# simulador.net
KiCad netlist of a schematic drawn in EAGLE
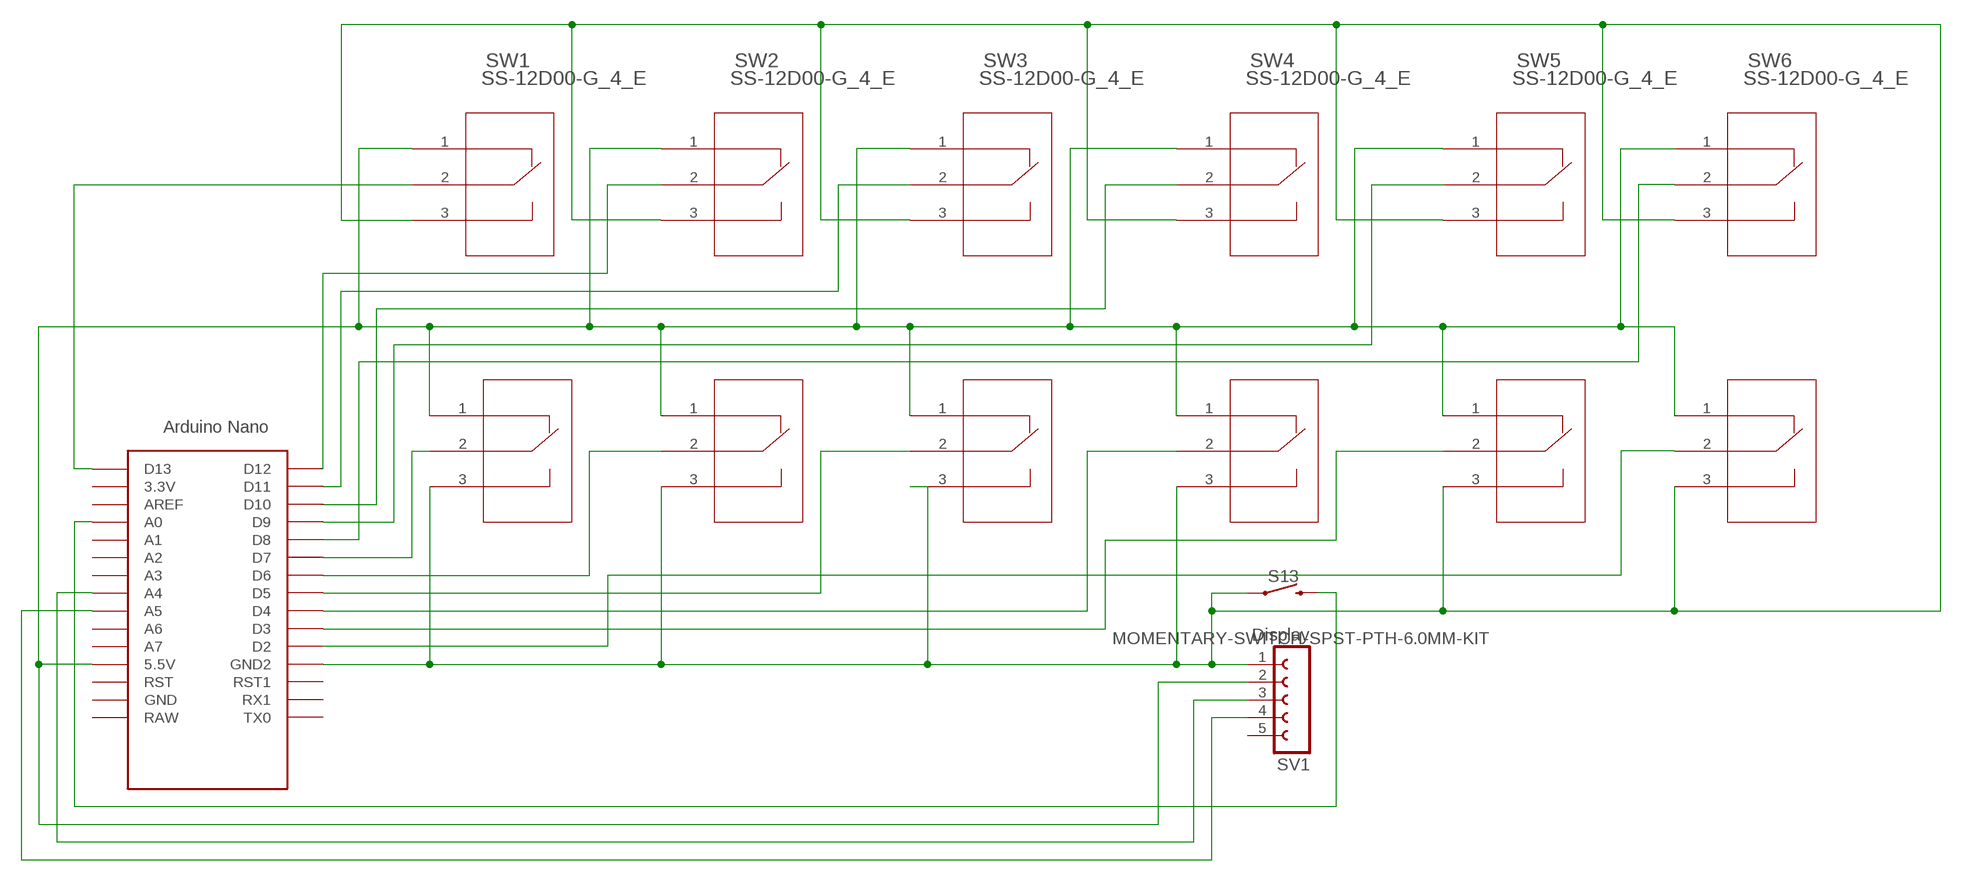
[diagram p0: schematic, sheet 1]

(export (version "E")
  (design (tool "Eeschema 10.0.6"))
  (components
    (comp (ref "S13")
      (value "MOMENTARY-SWITCH-SPST-PTH-6.0MM-KIT")
      (footprint "eagle-import:TACTILE_SWITCH_PTH_6.0MM_KIT")
      (libsource (lib "eagle-import") (part "MOMENTARY-SWITCH-SPST-PTH-6.0MM-KIT"))
    )
    (comp (ref "SV1")
      (value "Display")
      (footprint "eagle-import:FE05-1")
      (libsource (lib "eagle-import") (part "FE05-1"))
    )
    (comp (ref "SW1")
      (value "SS-12D00-G_4_E")
      (footprint "eagle-import:1P2T_SS-12D00_CNK")
      (fields
        (field (name "MANUFACTURER_PART_NUMBER") "SS-12D00-G 4 E")
        (field (name "COPYRIGHT") "Copyright (C) 2025 Ultra Librarian. All rights reserved.")
      )
      (libsource (lib "eagle-import") (part "SS-12D00-G_4_E"))
    )
    (comp (ref "SW2")
      (value "SS-12D00-G_4_E")
      (footprint "eagle-import:1P2T_SS-12D00_CNK")
      (fields
        (field (name "MANUFACTURER_PART_NUMBER") "SS-12D00-G 4 E")
        (field (name "COPYRIGHT") "Copyright (C) 2025 Ultra Librarian. All rights reserved.")
      )
      (libsource (lib "eagle-import") (part "SS-12D00-G_4_E"))
    )
    (comp (ref "SW3")
      (value "SS-12D00-G_4_E")
      (footprint "eagle-import:1P2T_SS-12D00_CNK")
      (fields
        (field (name "MANUFACTURER_PART_NUMBER") "SS-12D00-G 4 E")
        (field (name "COPYRIGHT") "Copyright (C) 2025 Ultra Librarian. All rights reserved.")
      )
      (libsource (lib "eagle-import") (part "SS-12D00-G_4_E"))
    )
    (comp (ref "SW4")
      (value "SS-12D00-G_4_E")
      (footprint "eagle-import:1P2T_SS-12D00_CNK")
      (fields
        (field (name "MANUFACTURER_PART_NUMBER") "SS-12D00-G 4 E")
        (field (name "COPYRIGHT") "Copyright (C) 2025 Ultra Librarian. All rights reserved.")
      )
      (libsource (lib "eagle-import") (part "SS-12D00-G_4_E"))
    )
    (comp (ref "SW5")
      (value "SS-12D00-G_4_E")
      (footprint "eagle-import:1P2T_SS-12D00_CNK")
      (fields
        (field (name "MANUFACTURER_PART_NUMBER") "SS-12D00-G 4 E")
        (field (name "COPYRIGHT") "Copyright (C) 2025 Ultra Librarian. All rights reserved.")
      )
      (libsource (lib "eagle-import") (part "SS-12D00-G_4_E"))
    )
    (comp (ref "SW6")
      (value "SS-12D00-G_4_E")
      (footprint "eagle-import:1P2T_SS-12D00_CNK")
      (fields
        (field (name "MANUFACTURER_PART_NUMBER") "SS-12D00-G 4 E")
        (field (name "COPYRIGHT") "Copyright (C) 2025 Ultra Librarian. All rights reserved.")
      )
      (libsource (lib "eagle-import") (part "SS-12D00-G_4_E"))
    )
    (comp (ref "SW7")
      (value "SS-12D00-G_4_E")
      (footprint "eagle-import:1P2T_SS-12D00_CNK")
      (fields
        (field (name "MANUFACTURER_PART_NUMBER") "SS-12D00-G 4 E")
        (field (name "COPYRIGHT") "Copyright (C) 2025 Ultra Librarian. All rights reserved.")
      )
      (libsource (lib "eagle-import") (part "SS-12D00-G_4_E"))
    )
    (comp (ref "SW8")
      (value "SS-12D00-G_4_E")
      (footprint "eagle-import:1P2T_SS-12D00_CNK")
      (fields
        (field (name "MANUFACTURER_PART_NUMBER") "SS-12D00-G 4 E")
        (field (name "COPYRIGHT") "Copyright (C) 2025 Ultra Librarian. All rights reserved.")
      )
      (libsource (lib "eagle-import") (part "SS-12D00-G_4_E"))
    )
    (comp (ref "SW9")
      (value "SS-12D00-G_4_E")
      (footprint "eagle-import:1P2T_SS-12D00_CNK")
      (fields
        (field (name "MANUFACTURER_PART_NUMBER") "SS-12D00-G 4 E")
        (field (name "COPYRIGHT") "Copyright (C) 2025 Ultra Librarian. All rights reserved.")
      )
      (libsource (lib "eagle-import") (part "SS-12D00-G_4_E"))
    )
    (comp (ref "SW10")
      (value "SS-12D00-G_4_E")
      (footprint "eagle-import:1P2T_SS-12D00_CNK")
      (fields
        (field (name "MANUFACTURER_PART_NUMBER") "SS-12D00-G 4 E")
        (field (name "COPYRIGHT") "Copyright (C) 2025 Ultra Librarian. All rights reserved.")
      )
      (libsource (lib "eagle-import") (part "SS-12D00-G_4_E"))
    )
    (comp (ref "SW11")
      (value "SS-12D00-G_4_E")
      (footprint "eagle-import:1P2T_SS-12D00_CNK")
      (fields
        (field (name "MANUFACTURER_PART_NUMBER") "SS-12D00-G 4 E")
        (field (name "COPYRIGHT") "Copyright (C) 2025 Ultra Librarian. All rights reserved.")
      )
      (libsource (lib "eagle-import") (part "SS-12D00-G_4_E"))
    )
    (comp (ref "SW12")
      (value "SS-12D00-G_4_E")
      (footprint "eagle-import:1P2T_SS-12D00_CNK")
      (fields
        (field (name "MANUFACTURER_PART_NUMBER") "SS-12D00-G 4 E")
        (field (name "COPYRIGHT") "Copyright (C) 2025 Ultra Librarian. All rights reserved.")
      )
      (libsource (lib "eagle-import") (part "SS-12D00-G_4_E"))
    )
    (comp (ref "U$1")
      (value "NANO")
      (footprint "eagle-import:NANO")
      (libsource (lib "eagle-import") (part "NANO"))
    )
  )
  (nets
    (net (code "1") (name "Net-(S13-2)") (class "Default")
      (node (ref "S13") (pin "3") (pinfunction "2_3") (pintype "passive"))
      (node (ref "U$1") (pin "A0") (pinfunction "A0_A0") (pintype "bidirectional"))
    )
    (net (code "2") (name "Net-(SV1-Pad3)") (class "Default")
      (node (ref "SV1") (pin "3") (pinfunction "3_3") (pintype "passive"))
      (node (ref "U$1") (pin "A4") (pinfunction "A4_A4") (pintype "bidirectional"))
    )
    (net (code "3") (name "Net-(SV1-Pad4)") (class "Default")
      (node (ref "SV1") (pin "4") (pinfunction "4_4") (pintype "passive"))
      (node (ref "U$1") (pin "A5") (pinfunction "A5_A5") (pintype "bidirectional"))
    )
    (net (code "4") (name "Net-(SW1-Pad2)") (class "Default")
      (node (ref "SW1") (pin "2") (pinfunction "2_2") (pintype "passive"))
      (node (ref "U$1") (pin "D13") (pinfunction "D13_D13") (pintype "bidirectional"))
    )
    (net (code "5") (name "Net-(SW2-Pad2)") (class "Default")
      (node (ref "SW2") (pin "2") (pinfunction "2_2") (pintype "passive"))
      (node (ref "U$1") (pin "D12") (pinfunction "D12_D12") (pintype "bidirectional"))
    )
    (net (code "6") (name "Net-(SW3-Pad2)") (class "Default")
      (node (ref "SW3") (pin "2") (pinfunction "2_2") (pintype "passive"))
      (node (ref "U$1") (pin "D11") (pinfunction "D11_D11") (pintype "bidirectional"))
    )
    (net (code "7") (name "Net-(SW4-Pad2)") (class "Default")
      (node (ref "SW4") (pin "2") (pinfunction "2_2") (pintype "passive"))
      (node (ref "U$1") (pin "D10") (pinfunction "D10_D10") (pintype "bidirectional"))
    )
    (net (code "8") (name "Net-(SW5-Pad2)") (class "Default")
      (node (ref "SW5") (pin "2") (pinfunction "2_2") (pintype "passive"))
      (node (ref "U$1") (pin "D9") (pinfunction "D9_D9") (pintype "bidirectional"))
    )
    (net (code "9") (name "Net-(SW6-Pad2)") (class "Default")
      (node (ref "SW6") (pin "2") (pinfunction "2_2") (pintype "passive"))
      (node (ref "U$1") (pin "D8") (pinfunction "D8_D8") (pintype "bidirectional"))
    )
    (net (code "10") (name "Net-(SW7-Pad2)") (class "Default")
      (node (ref "SW7") (pin "2") (pinfunction "2_2") (pintype "passive"))
      (node (ref "U$1") (pin "D7") (pinfunction "D7_D7") (pintype "bidirectional"))
    )
    (net (code "11") (name "Net-(SW8-Pad2)") (class "Default")
      (node (ref "SW8") (pin "2") (pinfunction "2_2") (pintype "passive"))
      (node (ref "U$1") (pin "D6") (pinfunction "D6_D6") (pintype "bidirectional"))
    )
    (net (code "12") (name "Net-(SW9-Pad2)") (class "Default")
      (node (ref "SW9") (pin "2") (pinfunction "2_2") (pintype "passive"))
      (node (ref "U$1") (pin "D5") (pinfunction "D5_D5") (pintype "bidirectional"))
    )
    (net (code "13") (name "Net-(SW10-Pad2)") (class "Default")
      (node (ref "SW10") (pin "2") (pinfunction "2_2") (pintype "passive"))
      (node (ref "U$1") (pin "D4") (pinfunction "D4_D4") (pintype "bidirectional"))
    )
    (net (code "14") (name "Net-(SW11-Pad2)") (class "Default")
      (node (ref "SW11") (pin "2") (pinfunction "2_2") (pintype "passive"))
      (node (ref "U$1") (pin "D3") (pinfunction "D3_D3") (pintype "bidirectional"))
    )
    (net (code "15") (name "Net-(SW12-Pad2)") (class "Default")
      (node (ref "SW12") (pin "2") (pinfunction "2_2") (pintype "passive"))
      (node (ref "U$1") (pin "D2") (pinfunction "D2_D2") (pintype "bidirectional"))
    )
    (net (code "16") (name "Net-(U$1-5.5V)") (class "Default")
      (node (ref "SV1") (pin "2") (pinfunction "2_2") (pintype "passive"))
      (node (ref "SW1") (pin "1") (pinfunction "1_1") (pintype "passive"))
      (node (ref "SW10") (pin "1") (pinfunction "1_1") (pintype "passive"))
      (node (ref "SW11") (pin "1") (pinfunction "1_1") (pintype "passive"))
      (node (ref "SW12") (pin "1") (pinfunction "1_1") (pintype "passive"))
      (node (ref "SW2") (pin "1") (pinfunction "1_1") (pintype "passive"))
      (node (ref "SW3") (pin "1") (pinfunction "1_1") (pintype "passive"))
      (node (ref "SW4") (pin "1") (pinfunction "1_1") (pintype "passive"))
      (node (ref "SW5") (pin "1") (pinfunction "1_1") (pintype "passive"))
      (node (ref "SW6") (pin "1") (pinfunction "1_1") (pintype "passive"))
      (node (ref "SW7") (pin "1") (pinfunction "1_1") (pintype "passive"))
      (node (ref "SW8") (pin "1") (pinfunction "1_1") (pintype "passive"))
      (node (ref "SW9") (pin "1") (pinfunction "1_1") (pintype "passive"))
      (node (ref "U$1") (pin "5V") (pinfunction "5.5V_5V") (pintype "bidirectional"))
    )
    (net (code "17") (name "Net-(U$1-GND2)") (class "Default")
      (node (ref "S13") (pin "1") (pinfunction "1_1") (pintype "passive"))
      (node (ref "SV1") (pin "1") (pinfunction "1_1") (pintype "passive"))
      (node (ref "SW1") (pin "3") (pinfunction "3_3") (pintype "passive"))
      (node (ref "SW10") (pin "3") (pinfunction "3_3") (pintype "passive"))
      (node (ref "SW11") (pin "3") (pinfunction "3_3") (pintype "passive"))
      (node (ref "SW12") (pin "3") (pinfunction "3_3") (pintype "passive"))
      (node (ref "SW2") (pin "3") (pinfunction "3_3") (pintype "passive"))
      (node (ref "SW3") (pin "3") (pinfunction "3_3") (pintype "passive"))
      (node (ref "SW4") (pin "3") (pinfunction "3_3") (pintype "passive"))
      (node (ref "SW5") (pin "3") (pinfunction "3_3") (pintype "passive"))
      (node (ref "SW6") (pin "3") (pinfunction "3_3") (pintype "passive"))
      (node (ref "SW7") (pin "3") (pinfunction "3_3") (pintype "passive"))
      (node (ref "SW8") (pin "3") (pinfunction "3_3") (pintype "passive"))
      (node (ref "SW9") (pin "3") (pinfunction "3_3") (pintype "passive"))
      (node (ref "U$1") (pin "GND1") (pinfunction "GND2_GND1") (pintype "bidirectional"))
    )
    (net (code "18") (name "unconnected-(SV1-Pad5)") (class "Default")
      (node (ref "SV1") (pin "5") (pinfunction "5_5") (pintype "passive"))
    )
    (net (code "19") (name "unconnected-(U$1-Pad3.3V)") (class "Default")
      (node (ref "U$1") (pin "3.3V") (pinfunction "3.3V_3.3V") (pintype "bidirectional"))
    )
    (net (code "20") (name "unconnected-(U$1-PadA1)") (class "Default")
      (node (ref "U$1") (pin "A1") (pinfunction "A1_A1") (pintype "bidirectional"))
    )
    (net (code "21") (name "unconnected-(U$1-PadA2)") (class "Default")
      (node (ref "U$1") (pin "A2") (pinfunction "A2_A2") (pintype "bidirectional"))
    )
    (net (code "22") (name "unconnected-(U$1-PadA3)") (class "Default")
      (node (ref "U$1") (pin "A3") (pinfunction "A3_A3") (pintype "bidirectional"))
    )
    (net (code "23") (name "unconnected-(U$1-PadA6)") (class "Default")
      (node (ref "U$1") (pin "A6") (pinfunction "A6_A6") (pintype "bidirectional"))
    )
    (net (code "24") (name "unconnected-(U$1-PadA7)") (class "Default")
      (node (ref "U$1") (pin "A7") (pinfunction "A7_A7") (pintype "bidirectional"))
    )
    (net (code "25") (name "unconnected-(U$1-PadAREF)") (class "Default")
      (node (ref "U$1") (pin "AREF") (pinfunction "AREF_AREF") (pintype "bidirectional"))
    )
    (net (code "26") (name "unconnected-(U$1-PadGND)") (class "Default")
      (node (ref "U$1") (pin "GND") (pinfunction "GND_GND") (pintype "bidirectional"))
    )
    (net (code "27") (name "unconnected-(U$1-PadICSP1)") (class "Default")
      (node (ref "U$1") (pin "ICSP1") (pinfunction "ICSP1_ICSP1") (pintype "bidirectional"))
    )
    (net (code "28") (name "unconnected-(U$1-PadICSP2)") (class "Default")
      (node (ref "U$1") (pin "ICSP2") (pinfunction "ICSP2_ICSP2") (pintype "bidirectional"))
    )
    (net (code "29") (name "unconnected-(U$1-PadICSP3)") (class "Default")
      (node (ref "U$1") (pin "ICSP3") (pinfunction "ICSP3_ICSP3") (pintype "bidirectional"))
    )
    (net (code "30") (name "unconnected-(U$1-PadICSP4)") (class "Default")
      (node (ref "U$1") (pin "ICSP4") (pinfunction "ICSP4_ICSP4") (pintype "bidirectional"))
    )
    (net (code "31") (name "unconnected-(U$1-PadICSP5)") (class "Default")
      (node (ref "U$1") (pin "ICSP5") (pinfunction "ICSP5_ICSP5") (pintype "bidirectional"))
    )
    (net (code "32") (name "unconnected-(U$1-PadICSP6)") (class "Default")
      (node (ref "U$1") (pin "ICSP6") (pinfunction "ICSP6_ICSP6") (pintype "bidirectional"))
    )
    (net (code "33") (name "unconnected-(U$1-PadRAW)") (class "Default")
      (node (ref "U$1") (pin "RAW") (pinfunction "RAW_RAW") (pintype "bidirectional"))
    )
    (net (code "34") (name "unconnected-(U$1-PadRST)") (class "Default")
      (node (ref "U$1") (pin "RST") (pinfunction "RST_RST") (pintype "bidirectional"))
    )
    (net (code "35") (name "unconnected-(U$1-PadRST1)") (class "Default")
      (node (ref "U$1") (pin "RST1") (pinfunction "RST1_RST1") (pintype "bidirectional"))
    )
    (net (code "36") (name "unconnected-(U$1-PadRX1)") (class "Default")
      (node (ref "U$1") (pin "RX1") (pinfunction "RX1_RX1") (pintype "bidirectional"))
    )
    (net (code "37") (name "unconnected-(U$1-PadTX0)") (class "Default")
      (node (ref "U$1") (pin "TX0") (pinfunction "TX0_TX0") (pintype "bidirectional"))
    )
  )
)
